# Massage_Pad_Peripheral_PCB_SplitPlane.net
KiCad netlist of a schematic drawn in EAGLE
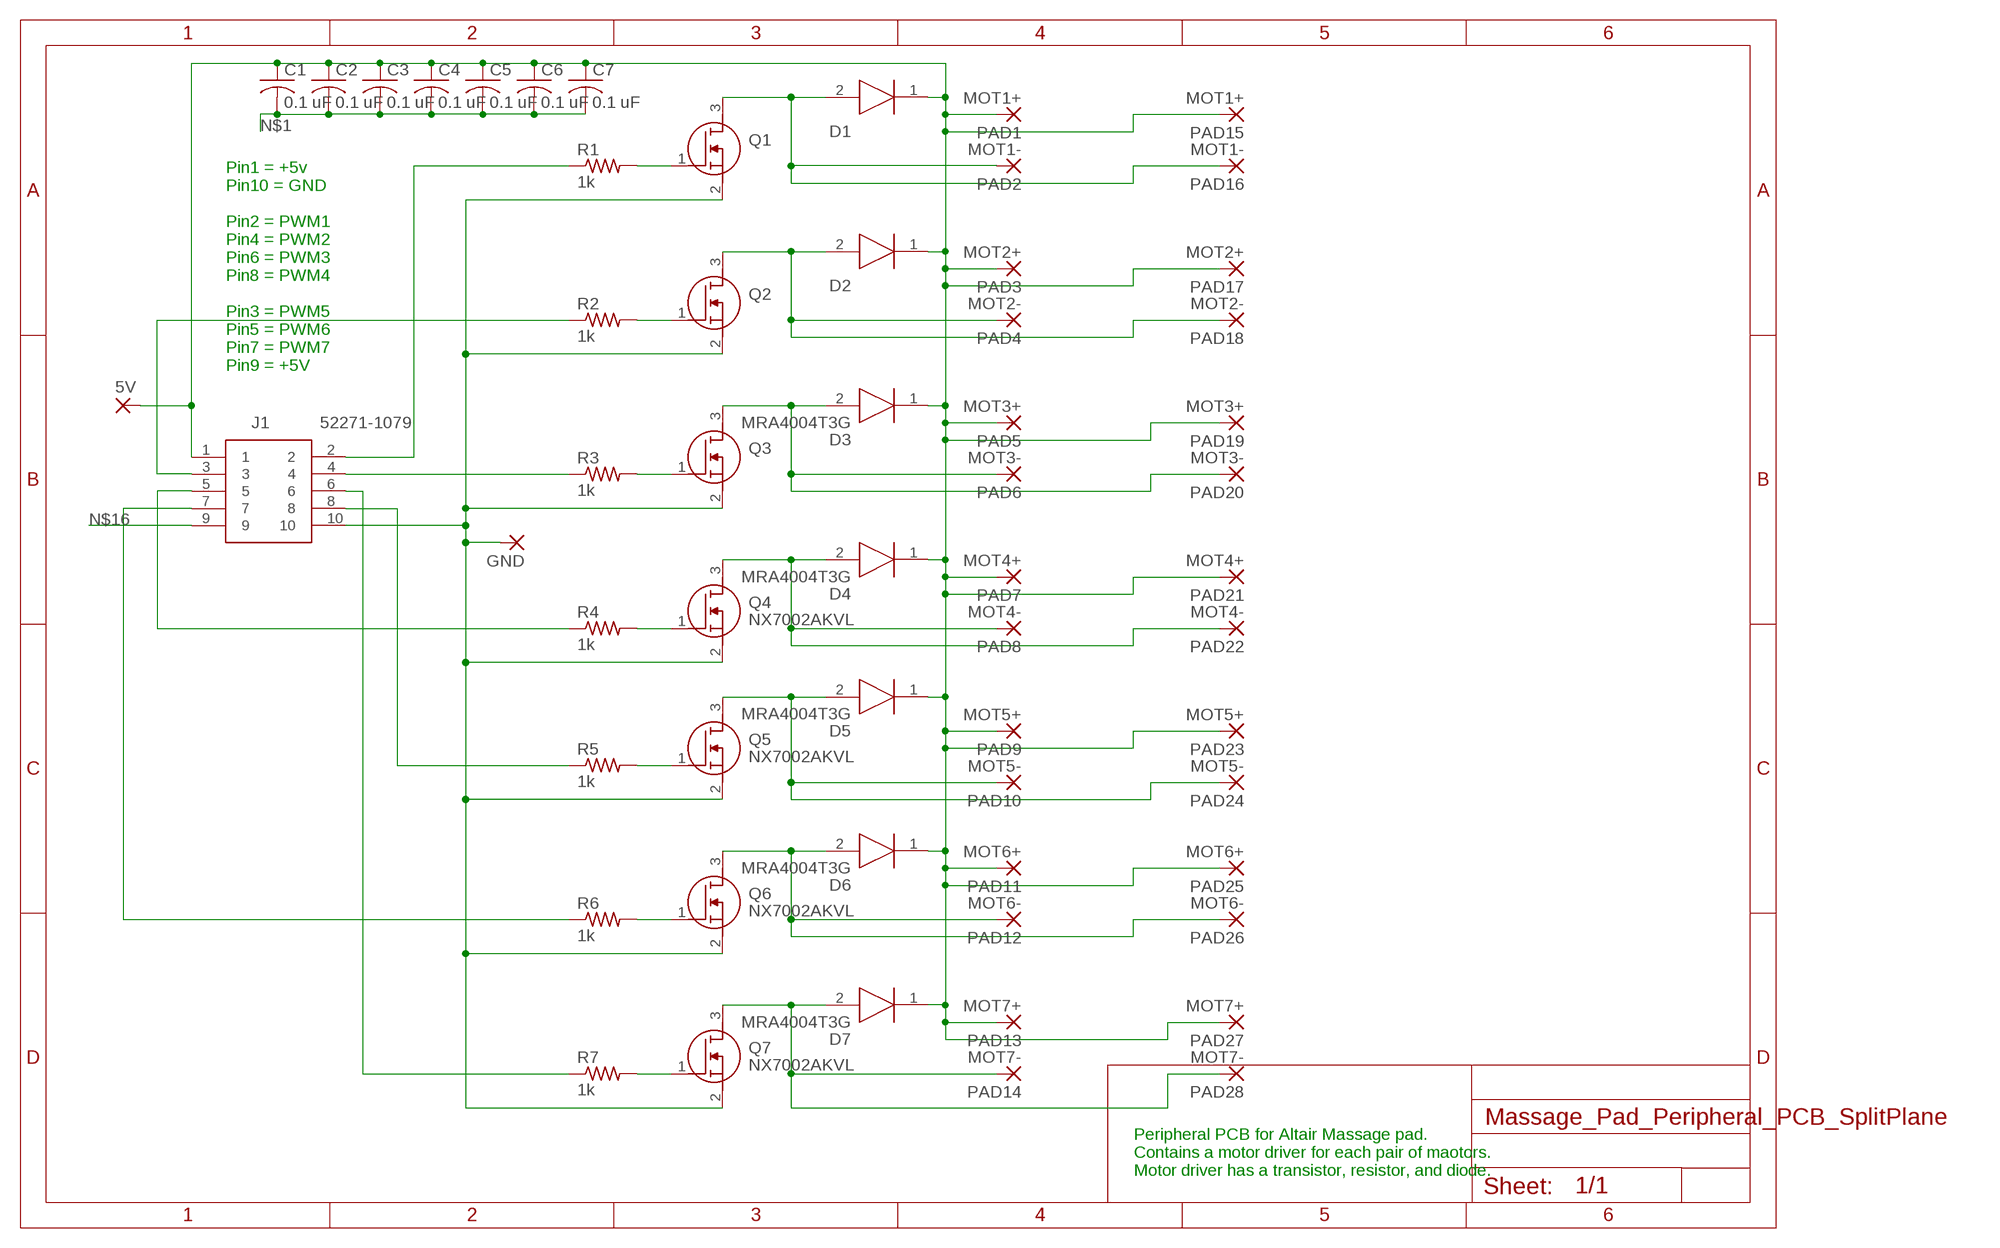
[diagram p0: schematic, sheet 1]

(export (version "E")
  (design (tool "Eeschema 10.0.6"))
  (components
    (comp (ref "5V")
      (value "3,17/1,3")
      (footprint "eagle-import:3,17_1,3")
      (libsource (lib "eagle-import") (part "3,17/1,3"))
    )
    (comp (ref "C1")
      (value "0.1 uF")
      (footprint "eagle-import:C1808")
      (fields
        (field (name "MANUFACTURER_PART_NUMBER") "C1808C104K5RACTU")
        (field (name "MOUSER_PART_NUMBER") "80-C1808C104K5R ")
      )
      (libsource (lib "eagle-import") (part "C-USC1808"))
    )
    (comp (ref "C2")
      (value "0.1 uF")
      (footprint "eagle-import:C1808")
      (fields
        (field (name "MANUFACTURER_PART_NUMBER") "C1808C104K5RACTU")
        (field (name "MOUSER_PART_NUMBER") "80-C1808C104K5R ")
      )
      (libsource (lib "eagle-import") (part "C-USC1808"))
    )
    (comp (ref "C3")
      (value "0.1 uF")
      (footprint "eagle-import:C1808")
      (fields
        (field (name "MANUFACTURER_PART_NUMBER") "C1808C104K5RACTU")
        (field (name "MOUSER_PART_NUMBER") "80-C1808C104K5R ")
      )
      (libsource (lib "eagle-import") (part "C-USC1808"))
    )
    (comp (ref "C4")
      (value "0.1 uF")
      (footprint "eagle-import:C1808")
      (fields
        (field (name "MANUFACTURER_PART_NUMBER") "C1808C104K5RACTU")
        (field (name "MOUSER_PART_NUMBER") "80-C1808C104K5R ")
      )
      (libsource (lib "eagle-import") (part "C-USC1808"))
    )
    (comp (ref "C5")
      (value "0.1 uF")
      (footprint "eagle-import:C1808")
      (fields
        (field (name "MANUFACTURER_PART_NUMBER") "C1808C104K5RACTU")
        (field (name "MOUSER_PART_NUMBER") "80-C1808C104K5R")
      )
      (libsource (lib "eagle-import") (part "C-USC1808"))
    )
    (comp (ref "C6")
      (value "0.1 uF")
      (footprint "eagle-import:C1808")
      (fields
        (field (name "MANUFACTURER_PART_NUMBER") "C1808C104K5RACTU")
        (field (name "MOUSER_PART_NUMBER") "80-C1808C104K5R ")
      )
      (libsource (lib "eagle-import") (part "C-USC1808"))
    )
    (comp (ref "C7")
      (value "0.1 uF")
      (footprint "eagle-import:C1808")
      (fields
        (field (name "MANUFACTURER_PART_NUMBER") "C1808C104K5RACTU")
        (field (name "MOUSER_PART_NUMBER") "80-C1808C104K5R")
      )
      (libsource (lib "eagle-import") (part "C-USC1808"))
    )
    (comp (ref "D1")
      (value "MRA4004T3G")
      (footprint "eagle-import:DIOM5226X220N")
      (fields (field (name "MOUSER_PART_NUMBER") "863-MRA4004T3G") (field (name "RS_PART_NUMBER") "6490904"))
      (libsource (lib "eagle-import") (part "MRA4004T3G"))
    )
    (comp (ref "D2")
      (value "MRA4004T3G")
      (footprint "eagle-import:DIOM5226X220N")
      (fields (field (name "MOUSER_PART_NUMBER") "863-MRA4004T3G") (field (name "RS_PART_NUMBER") "6490904"))
      (libsource (lib "eagle-import") (part "MRA4004T3G"))
    )
    (comp (ref "D3")
      (value "MRA4004T3G")
      (footprint "eagle-import:DIOM5226X220N")
      (fields (field (name "MOUSER_PART_NUMBER") "863-MRA4004T3G") (field (name "RS_PART_NUMBER") "6490904"))
      (libsource (lib "eagle-import") (part "MRA4004T3G"))
    )
    (comp (ref "D4")
      (value "MRA4004T3G")
      (footprint "eagle-import:DIOM5226X220N")
      (fields (field (name "MOUSER_PART_NUMBER") "863-MRA4004T3G") (field (name "RS_PART_NUMBER") "6490904"))
      (libsource (lib "eagle-import") (part "MRA4004T3G"))
    )
    (comp (ref "D5")
      (value "MRA4004T3G")
      (footprint "eagle-import:DIOM5226X220N")
      (fields (field (name "MOUSER_PART_NUMBER") "863-MRA4004T3G") (field (name "RS_PART_NUMBER") "6490904"))
      (libsource (lib "eagle-import") (part "MRA4004T3G"))
    )
    (comp (ref "D6")
      (value "MRA4004T3G")
      (footprint "eagle-import:DIOM5226X220N")
      (fields (field (name "MOUSER_PART_NUMBER") "863-MRA4004T3G") (field (name "RS_PART_NUMBER") "6490904"))
      (libsource (lib "eagle-import") (part "MRA4004T3G"))
    )
    (comp (ref "D7")
      (value "MRA4004T3G")
      (footprint "eagle-import:DIOM5226X220N")
      (fields (field (name "MOUSER_PART_NUMBER") "863-MRA4004T3G") (field (name "RS_PART_NUMBER") "6490904"))
      (libsource (lib "eagle-import") (part "MRA4004T3G"))
    )
    (comp (ref "GND")
      (value "3,17/1,3")
      (footprint "eagle-import:3,17_1,3")
      (libsource (lib "eagle-import") (part "3,17/1,3"))
    )
    (comp (ref "J1")
      (value "52271-1079")
      (footprint "eagle-import:52271-1079")
      (fields (field (name "MOUSER_PART_NUMBER") "538-52271-1079") (field (name "RS_PART_NUMBER") "5144329P"))
      (libsource (lib "eagle-import") (part "52271-1079"))
    )
    (comp (ref "PAD1")
      (value "MOT1+")
      (footprint "eagle-import:5-2,5")
      (libsource (lib "eagle-import") (part "WIREPADSMD5-2,5"))
    )
    (comp (ref "PAD2")
      (value "MOT1-")
      (footprint "eagle-import:5-2,5")
      (libsource (lib "eagle-import") (part "WIREPADSMD5-2,5"))
    )
    (comp (ref "PAD3")
      (value "MOT2+")
      (footprint "eagle-import:5-2,5")
      (libsource (lib "eagle-import") (part "WIREPADSMD5-2,5"))
    )
    (comp (ref "PAD4")
      (value "MOT2-")
      (footprint "eagle-import:5-2,5")
      (libsource (lib "eagle-import") (part "WIREPADSMD5-2,5"))
    )
    (comp (ref "PAD5")
      (value "MOT3+")
      (footprint "eagle-import:5-2,5")
      (libsource (lib "eagle-import") (part "WIREPADSMD5-2,5"))
    )
    (comp (ref "PAD6")
      (value "MOT3-")
      (footprint "eagle-import:5-2,5")
      (libsource (lib "eagle-import") (part "WIREPADSMD5-2,5"))
    )
    (comp (ref "PAD7")
      (value "MOT4+")
      (footprint "eagle-import:5-2,5")
      (libsource (lib "eagle-import") (part "WIREPADSMD5-2,5"))
    )
    (comp (ref "PAD8")
      (value "MOT4-")
      (footprint "eagle-import:5-2,5")
      (libsource (lib "eagle-import") (part "WIREPADSMD5-2,5"))
    )
    (comp (ref "PAD9")
      (value "MOT5+")
      (footprint "eagle-import:5-2,5")
      (libsource (lib "eagle-import") (part "WIREPADSMD5-2,5"))
    )
    (comp (ref "PAD10")
      (value "MOT5-")
      (footprint "eagle-import:5-2,5")
      (libsource (lib "eagle-import") (part "WIREPADSMD5-2,5"))
    )
    (comp (ref "PAD11")
      (value "MOT6+")
      (footprint "eagle-import:5-2,5")
      (libsource (lib "eagle-import") (part "WIREPADSMD5-2,5"))
    )
    (comp (ref "PAD12")
      (value "MOT6-")
      (footprint "eagle-import:5-2,5")
      (libsource (lib "eagle-import") (part "WIREPADSMD5-2,5"))
    )
    (comp (ref "PAD13")
      (value "MOT7+")
      (footprint "eagle-import:5-2,5")
      (libsource (lib "eagle-import") (part "WIREPADSMD5-2,5"))
    )
    (comp (ref "PAD14")
      (value "MOT7-")
      (footprint "eagle-import:5-2,5")
      (libsource (lib "eagle-import") (part "WIREPADSMD5-2,5"))
    )
    (comp (ref "PAD15")
      (value "MOT1+")
      (footprint "eagle-import:5-2,5")
      (libsource (lib "eagle-import") (part "WIREPADSMD5-2,5"))
    )
    (comp (ref "PAD16")
      (value "MOT1-")
      (footprint "eagle-import:5-2,5")
      (libsource (lib "eagle-import") (part "WIREPADSMD5-2,5"))
    )
    (comp (ref "PAD17")
      (value "MOT2+")
      (footprint "eagle-import:5-2,5")
      (libsource (lib "eagle-import") (part "WIREPADSMD5-2,5"))
    )
    (comp (ref "PAD18")
      (value "MOT2-")
      (footprint "eagle-import:5-2,5")
      (libsource (lib "eagle-import") (part "WIREPADSMD5-2,5"))
    )
    (comp (ref "PAD19")
      (value "MOT3+")
      (footprint "eagle-import:5-2,5")
      (libsource (lib "eagle-import") (part "WIREPADSMD5-2,5"))
    )
    (comp (ref "PAD20")
      (value "MOT3-")
      (footprint "eagle-import:5-2,5")
      (libsource (lib "eagle-import") (part "WIREPADSMD5-2,5"))
    )
    (comp (ref "PAD21")
      (value "MOT4+")
      (footprint "eagle-import:5-2,5")
      (libsource (lib "eagle-import") (part "WIREPADSMD5-2,5"))
    )
    (comp (ref "PAD22")
      (value "MOT4-")
      (footprint "eagle-import:5-2,5")
      (libsource (lib "eagle-import") (part "WIREPADSMD5-2,5"))
    )
    (comp (ref "PAD23")
      (value "MOT5+")
      (footprint "eagle-import:5-2,5")
      (libsource (lib "eagle-import") (part "WIREPADSMD5-2,5"))
    )
    (comp (ref "PAD24")
      (value "MOT5-")
      (footprint "eagle-import:5-2,5")
      (libsource (lib "eagle-import") (part "WIREPADSMD5-2,5"))
    )
    (comp (ref "PAD25")
      (value "MOT6+")
      (footprint "eagle-import:5-2,5")
      (libsource (lib "eagle-import") (part "WIREPADSMD5-2,5"))
    )
    (comp (ref "PAD26")
      (value "MOT6-")
      (footprint "eagle-import:5-2,5")
      (libsource (lib "eagle-import") (part "WIREPADSMD5-2,5"))
    )
    (comp (ref "PAD27")
      (value "MOT7+")
      (footprint "eagle-import:5-2,5")
      (libsource (lib "eagle-import") (part "WIREPADSMD5-2,5"))
    )
    (comp (ref "PAD28")
      (value "MOT7-")
      (footprint "eagle-import:5-2,5")
      (libsource (lib "eagle-import") (part "WIREPADSMD5-2,5"))
    )
    (comp (ref "Q1")
      (value "NX7002AKVL")
      (footprint "eagle-import:SOT95P230X110-3N")
      (fields (field (name "MOUSER_PART_NUMBER") "771-NX7002AKVL"))
      (libsource (lib "eagle-import") (part "NX7002AKVL"))
    )
    (comp (ref "Q2")
      (value "NX7002AKVL")
      (footprint "eagle-import:SOT95P230X110-3N")
      (fields (field (name "MOUSER_PART_NUMBER") "771-NX7002AKVL"))
      (libsource (lib "eagle-import") (part "NX7002AKVL"))
    )
    (comp (ref "Q3")
      (value "NX7002AKVL")
      (footprint "eagle-import:SOT95P230X110-3N")
      (fields (field (name "MOUSER_PART_NUMBER") "771-NX7002AKVL"))
      (libsource (lib "eagle-import") (part "NX7002AKVL"))
    )
    (comp (ref "Q4")
      (value "NX7002AKVL")
      (footprint "eagle-import:SOT95P230X110-3N")
      (fields (field (name "MOUSER_PART_NUMBER") "771-NX7002AKVL"))
      (libsource (lib "eagle-import") (part "NX7002AKVL"))
    )
    (comp (ref "Q5")
      (value "NX7002AKVL")
      (footprint "eagle-import:SOT95P230X110-3N")
      (fields (field (name "MOUSER_PART_NUMBER") "771-NX7002AKVL"))
      (libsource (lib "eagle-import") (part "NX7002AKVL"))
    )
    (comp (ref "Q6")
      (value "NX7002AKVL")
      (footprint "eagle-import:SOT95P230X110-3N")
      (fields (field (name "MOUSER_PART_NUMBER") "771-NX7002AKVL"))
      (libsource (lib "eagle-import") (part "NX7002AKVL"))
    )
    (comp (ref "Q7")
      (value "NX7002AKVL")
      (footprint "eagle-import:SOT95P230X110-3N")
      (fields (field (name "MOUSER_PART_NUMBER") "771-NX7002AKVL"))
      (libsource (lib "eagle-import") (part "NX7002AKVL"))
    )
    (comp (ref "R1")
      (value "1k")
      (footprint "eagle-import:R1206")
      (fields
        (field (name "MANUFACTURER_PART_NUMBER") "CR1206-FX-1001ELF")
        (field (name "MOUSER_PART_NUMBER") "652-CR1206FX-1001ELF")
      )
      (libsource (lib "eagle-import") (part "R-US_R1206"))
    )
    (comp (ref "R2")
      (value "1k")
      (footprint "eagle-import:R1206")
      (libsource (lib "eagle-import") (part "R-US_R1206"))
    )
    (comp (ref "R3")
      (value "1k")
      (footprint "eagle-import:R1206")
      (libsource (lib "eagle-import") (part "R-US_R1206"))
    )
    (comp (ref "R4")
      (value "1k")
      (footprint "eagle-import:R1206")
      (libsource (lib "eagle-import") (part "R-US_R1206"))
    )
    (comp (ref "R5")
      (value "1k")
      (footprint "eagle-import:R1206")
      (libsource (lib "eagle-import") (part "R-US_R1206"))
    )
    (comp (ref "R6")
      (value "1k")
      (footprint "eagle-import:R1206")
      (libsource (lib "eagle-import") (part "R-US_R1206"))
    )
    (comp (ref "R7")
      (value "1k")
      (footprint "eagle-import:R1206")
      (libsource (lib "eagle-import") (part "R-US_R1206"))
    )
  )
  (nets
    (net (code "1") (name "/N$1") (class "Default")
      (node (ref "C1") (pin "2") (pinfunction "2_2") (pintype "passive"))
      (node (ref "C2") (pin "2") (pinfunction "2_2") (pintype "passive"))
      (node (ref "C3") (pin "2") (pinfunction "2_2") (pintype "passive"))
      (node (ref "C4") (pin "2") (pinfunction "2_2") (pintype "passive"))
      (node (ref "C5") (pin "2") (pinfunction "2_2") (pintype "passive"))
      (node (ref "C6") (pin "2") (pinfunction "2_2") (pintype "passive"))
      (node (ref "C7") (pin "2") (pinfunction "2_2") (pintype "passive"))
      (node (ref "GND") (pin "1") (pinfunction "P_1") (pintype "passive"))
      (node (ref "J1") (pin "10") (pinfunction "10_10") (pintype "bidirectional"))
      (node (ref "Q1") (pin "2") (pinfunction "S_2") (pintype "bidirectional"))
      (node (ref "Q2") (pin "2") (pinfunction "S_2") (pintype "bidirectional"))
      (node (ref "Q3") (pin "2") (pinfunction "S_2") (pintype "bidirectional"))
      (node (ref "Q4") (pin "2") (pinfunction "S_2") (pintype "bidirectional"))
      (node (ref "Q5") (pin "2") (pinfunction "S_2") (pintype "bidirectional"))
      (node (ref "Q6") (pin "2") (pinfunction "S_2") (pintype "bidirectional"))
      (node (ref "Q7") (pin "2") (pinfunction "S_2") (pintype "bidirectional"))
    )
    (net (code "2") (name "/N$16") (class "Default")
      (node (ref "5V") (pin "1") (pinfunction "P_1") (pintype "passive"))
      (node (ref "C1") (pin "1") (pinfunction "1_1") (pintype "passive"))
      (node (ref "C2") (pin "1") (pinfunction "1_1") (pintype "passive"))
      (node (ref "C3") (pin "1") (pinfunction "1_1") (pintype "passive"))
      (node (ref "C4") (pin "1") (pinfunction "1_1") (pintype "passive"))
      (node (ref "C5") (pin "1") (pinfunction "1_1") (pintype "passive"))
      (node (ref "C6") (pin "1") (pinfunction "1_1") (pintype "passive"))
      (node (ref "C7") (pin "1") (pinfunction "1_1") (pintype "passive"))
      (node (ref "D1") (pin "1") (pinfunction "K_1") (pintype "bidirectional"))
      (node (ref "D2") (pin "1") (pinfunction "K_1") (pintype "bidirectional"))
      (node (ref "D3") (pin "1") (pinfunction "K_1") (pintype "bidirectional"))
      (node (ref "D4") (pin "1") (pinfunction "K_1") (pintype "bidirectional"))
      (node (ref "D5") (pin "1") (pinfunction "K_1") (pintype "bidirectional"))
      (node (ref "D6") (pin "1") (pinfunction "K_1") (pintype "bidirectional"))
      (node (ref "D7") (pin "1") (pinfunction "K_1") (pintype "bidirectional"))
      (node (ref "J1") (pin "1") (pinfunction "1_1") (pintype "bidirectional"))
      (node (ref "J1") (pin "9") (pinfunction "9_9") (pintype "bidirectional"))
      (node (ref "PAD1") (pin "1") (pinfunction "P_1") (pintype "passive"))
      (node (ref "PAD11") (pin "1") (pinfunction "P_1") (pintype "passive"))
      (node (ref "PAD13") (pin "1") (pinfunction "P_1") (pintype "passive"))
      (node (ref "PAD15") (pin "1") (pinfunction "P_1") (pintype "passive"))
      (node (ref "PAD17") (pin "1") (pinfunction "P_1") (pintype "passive"))
      (node (ref "PAD19") (pin "1") (pinfunction "P_1") (pintype "passive"))
      (node (ref "PAD21") (pin "1") (pinfunction "P_1") (pintype "passive"))
      (node (ref "PAD23") (pin "1") (pinfunction "P_1") (pintype "passive"))
      (node (ref "PAD25") (pin "1") (pinfunction "P_1") (pintype "passive"))
      (node (ref "PAD27") (pin "1") (pinfunction "P_1") (pintype "passive"))
      (node (ref "PAD3") (pin "1") (pinfunction "P_1") (pintype "passive"))
      (node (ref "PAD5") (pin "1") (pinfunction "P_1") (pintype "passive"))
      (node (ref "PAD7") (pin "1") (pinfunction "P_1") (pintype "passive"))
      (node (ref "PAD9") (pin "1") (pinfunction "P_1") (pintype "passive"))
    )
    (net (code "3") (name "Net-(D1-A)") (class "Default")
      (node (ref "D1") (pin "2") (pinfunction "A_2") (pintype "bidirectional"))
      (node (ref "PAD16") (pin "1") (pinfunction "P_1") (pintype "passive"))
      (node (ref "PAD2") (pin "1") (pinfunction "P_1") (pintype "passive"))
      (node (ref "Q1") (pin "3") (pinfunction "D_3") (pintype "bidirectional"))
    )
    (net (code "4") (name "Net-(D2-A)") (class "Default")
      (node (ref "D2") (pin "2") (pinfunction "A_2") (pintype "bidirectional"))
      (node (ref "PAD18") (pin "1") (pinfunction "P_1") (pintype "passive"))
      (node (ref "PAD4") (pin "1") (pinfunction "P_1") (pintype "passive"))
      (node (ref "Q2") (pin "3") (pinfunction "D_3") (pintype "bidirectional"))
    )
    (net (code "5") (name "Net-(D3-A)") (class "Default")
      (node (ref "D3") (pin "2") (pinfunction "A_2") (pintype "bidirectional"))
      (node (ref "PAD20") (pin "1") (pinfunction "P_1") (pintype "passive"))
      (node (ref "PAD6") (pin "1") (pinfunction "P_1") (pintype "passive"))
      (node (ref "Q3") (pin "3") (pinfunction "D_3") (pintype "bidirectional"))
    )
    (net (code "6") (name "Net-(D4-A)") (class "Default")
      (node (ref "D4") (pin "2") (pinfunction "A_2") (pintype "bidirectional"))
      (node (ref "PAD22") (pin "1") (pinfunction "P_1") (pintype "passive"))
      (node (ref "PAD8") (pin "1") (pinfunction "P_1") (pintype "passive"))
      (node (ref "Q4") (pin "3") (pinfunction "D_3") (pintype "bidirectional"))
    )
    (net (code "7") (name "Net-(D5-A)") (class "Default")
      (node (ref "D5") (pin "2") (pinfunction "A_2") (pintype "bidirectional"))
      (node (ref "PAD10") (pin "1") (pinfunction "P_1") (pintype "passive"))
      (node (ref "PAD24") (pin "1") (pinfunction "P_1") (pintype "passive"))
      (node (ref "Q5") (pin "3") (pinfunction "D_3") (pintype "bidirectional"))
    )
    (net (code "8") (name "Net-(D6-A)") (class "Default")
      (node (ref "D6") (pin "2") (pinfunction "A_2") (pintype "bidirectional"))
      (node (ref "PAD12") (pin "1") (pinfunction "P_1") (pintype "passive"))
      (node (ref "PAD26") (pin "1") (pinfunction "P_1") (pintype "passive"))
      (node (ref "Q6") (pin "3") (pinfunction "D_3") (pintype "bidirectional"))
    )
    (net (code "9") (name "Net-(D7-A)") (class "Default")
      (node (ref "D7") (pin "2") (pinfunction "A_2") (pintype "bidirectional"))
      (node (ref "PAD14") (pin "1") (pinfunction "P_1") (pintype "passive"))
      (node (ref "PAD28") (pin "1") (pinfunction "P_1") (pintype "passive"))
      (node (ref "Q7") (pin "3") (pinfunction "D_3") (pintype "bidirectional"))
    )
    (net (code "10") (name "Net-(J1-Pad2)") (class "Default")
      (node (ref "J1") (pin "2") (pinfunction "2_2") (pintype "bidirectional"))
      (node (ref "R1") (pin "1") (pinfunction "1_1") (pintype "passive"))
    )
    (net (code "11") (name "Net-(J1-Pad3)") (class "Default")
      (node (ref "J1") (pin "3") (pinfunction "3_3") (pintype "bidirectional"))
      (node (ref "R2") (pin "1") (pinfunction "1_1") (pintype "passive"))
    )
    (net (code "12") (name "Net-(J1-Pad4)") (class "Default")
      (node (ref "J1") (pin "4") (pinfunction "4_4") (pintype "bidirectional"))
      (node (ref "R3") (pin "1") (pinfunction "1_1") (pintype "passive"))
    )
    (net (code "13") (name "Net-(J1-Pad5)") (class "Default")
      (node (ref "J1") (pin "5") (pinfunction "5_5") (pintype "bidirectional"))
      (node (ref "R4") (pin "1") (pinfunction "1_1") (pintype "passive"))
    )
    (net (code "14") (name "Net-(J1-Pad6)") (class "Default")
      (node (ref "J1") (pin "6") (pinfunction "6_6") (pintype "bidirectional"))
      (node (ref "R7") (pin "1") (pinfunction "1_1") (pintype "passive"))
    )
    (net (code "15") (name "Net-(J1-Pad7)") (class "Default")
      (node (ref "J1") (pin "7") (pinfunction "7_7") (pintype "bidirectional"))
      (node (ref "R6") (pin "1") (pinfunction "1_1") (pintype "passive"))
    )
    (net (code "16") (name "Net-(J1-Pad8)") (class "Default")
      (node (ref "J1") (pin "8") (pinfunction "8_8") (pintype "bidirectional"))
      (node (ref "R5") (pin "1") (pinfunction "1_1") (pintype "passive"))
    )
    (net (code "17") (name "Net-(Q1-G)") (class "Default")
      (node (ref "Q1") (pin "1") (pinfunction "G_1") (pintype "bidirectional"))
      (node (ref "R1") (pin "2") (pinfunction "2_2") (pintype "passive"))
    )
    (net (code "18") (name "Net-(Q2-G)") (class "Default")
      (node (ref "Q2") (pin "1") (pinfunction "G_1") (pintype "bidirectional"))
      (node (ref "R2") (pin "2") (pinfunction "2_2") (pintype "passive"))
    )
    (net (code "19") (name "Net-(Q3-G)") (class "Default")
      (node (ref "Q3") (pin "1") (pinfunction "G_1") (pintype "bidirectional"))
      (node (ref "R3") (pin "2") (pinfunction "2_2") (pintype "passive"))
    )
    (net (code "20") (name "Net-(Q4-G)") (class "Default")
      (node (ref "Q4") (pin "1") (pinfunction "G_1") (pintype "bidirectional"))
      (node (ref "R4") (pin "2") (pinfunction "2_2") (pintype "passive"))
    )
    (net (code "21") (name "Net-(Q5-G)") (class "Default")
      (node (ref "Q5") (pin "1") (pinfunction "G_1") (pintype "bidirectional"))
      (node (ref "R5") (pin "2") (pinfunction "2_2") (pintype "passive"))
    )
    (net (code "22") (name "Net-(Q6-G)") (class "Default")
      (node (ref "Q6") (pin "1") (pinfunction "G_1") (pintype "bidirectional"))
      (node (ref "R6") (pin "2") (pinfunction "2_2") (pintype "passive"))
    )
    (net (code "23") (name "Net-(Q7-G)") (class "Default")
      (node (ref "Q7") (pin "1") (pinfunction "G_1") (pintype "bidirectional"))
      (node (ref "R7") (pin "2") (pinfunction "2_2") (pintype "passive"))
    )
  )
)
